# ltk-hall_main_gauss.net
KiCad netlist of a schematic drawn in Altium Designer
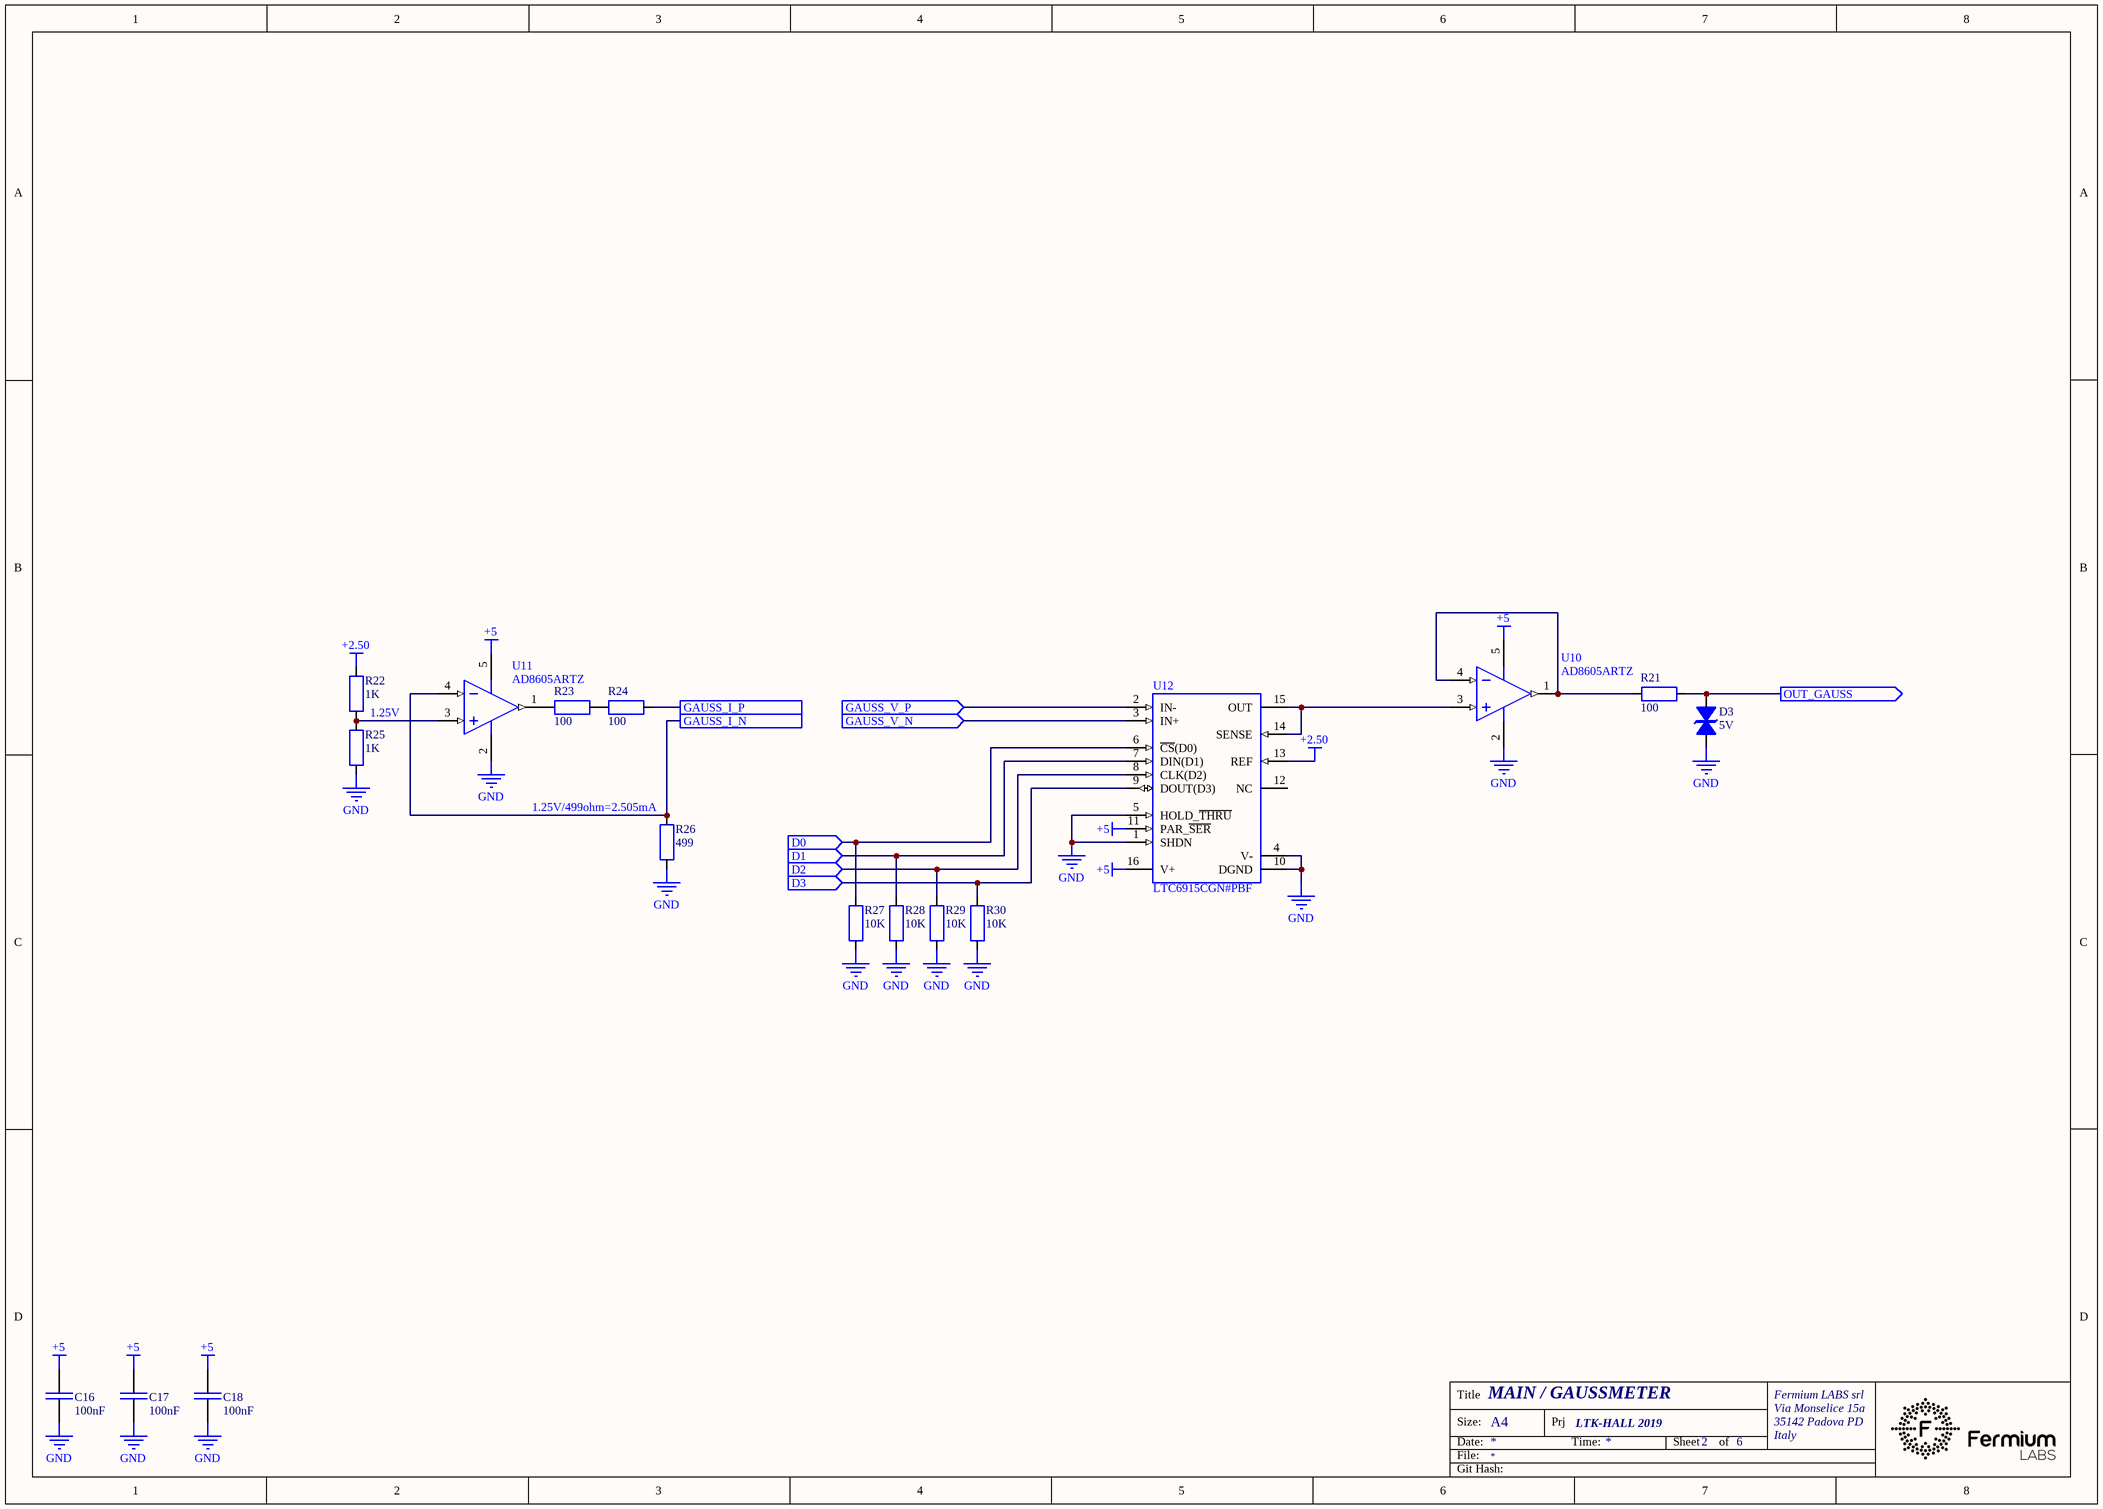
[diagram p0: ltk-hall_main_gauss.SchDoc]

(export (version "E")
  (design (tool "Eeschema 10.0.6"))
  (components
    (comp (ref "C16")
      (value "100nF")
      (footprint "CAP 0603_1608")
      (description "CAP SMD MLCC 100nF 25V 0603 X7R")
      (fields (field (name "PART NUMBER") "02841f84-ac15-41b5-9e17-915f8f067828"))
      (libsource (lib "frmdblib") (part "GENERIC_C"))
    )
    (comp (ref "C17")
      (value "100nF")
      (footprint "CAP 0603_1608")
      (description "CAP SMD MLCC 100nF 25V 0603 X7R")
      (fields (field (name "PART NUMBER") "02841f84-ac15-41b5-9e17-915f8f067828"))
      (libsource (lib "frmdblib") (part "GENERIC_C"))
    )
    (comp (ref "C18")
      (value "100nF")
      (footprint "CAP 0603_1608")
      (description "CAP SMD MLCC 100nF 25V 0603 X7R")
      (fields (field (name "PART NUMBER") "02841f84-ac15-41b5-9e17-915f8f067828"))
      (libsource (lib "frmdblib") (part "GENERIC_C"))
    )
    (comp (ref "D3")
      (value "5V")
      (footprint "SOD523F")
      (description "DIODE SMD TVS 5V BIDIRECTIONAL SOD-523")
      (fields (field (name "PART NUMBER") "daa58212-38e2-4326-a156-8e48058c46f1"))
      (libsource (lib "frmdblib") (part "GENERIC_D_TVS_BI"))
    )
    (comp (ref "R21")
      (value "100")
      (footprint "RES 0603_1608")
      (description "RES SMD 100 OHM 1% 1/10W 0603")
      (fields (field (name "PART NUMBER") "0a6c4b74-f837-4563-b154-6e196d753525"))
      (libsource (lib "frmdblib") (part "GENERIC_R"))
    )
    (comp (ref "R22")
      (value "1K")
      (footprint "RES 0603_1608")
      (description "RES SMD 1K OHM 1% 1/10W 0603")
      (fields (field (name "PART NUMBER") "a678220f-9e9d-4863-a833-9993504f723c"))
      (libsource (lib "frmdblib") (part "GENERIC_R"))
    )
    (comp (ref "R23")
      (value "100")
      (footprint "RES 0603_1608")
      (description "RES SMD 100 OHM 1% 1/10W 0603")
      (fields (field (name "PART NUMBER") "0a6c4b74-f837-4563-b154-6e196d753525"))
      (libsource (lib "frmdblib") (part "GENERIC_R"))
    )
    (comp (ref "R24")
      (value "100")
      (footprint "RES 0603_1608")
      (description "RES SMD 100 OHM 1% 1/10W 0603")
      (fields (field (name "PART NUMBER") "0a6c4b74-f837-4563-b154-6e196d753525"))
      (libsource (lib "frmdblib") (part "GENERIC_R"))
    )
    (comp (ref "R25")
      (value "1K")
      (footprint "RES 0603_1608")
      (description "RES SMD 1K OHM 1% 1/10W 0603")
      (fields (field (name "PART NUMBER") "a678220f-9e9d-4863-a833-9993504f723c"))
      (libsource (lib "frmdblib") (part "GENERIC_R"))
    )
    (comp (ref "R26")
      (value "499")
      (footprint "RES 0603_1608")
      (description "RES SMD 499 OHM 1% 1/10W 0603")
      (fields (field (name "PART NUMBER") "3a10051a-dd65-4121-b0b9-1b40351a1843"))
      (libsource (lib "frmdblib") (part "GENERIC_R"))
    )
    (comp (ref "R27")
      (value "10K")
      (footprint "RES 0603_1608")
      (description "RES SMD 10K OHM 1% 1/10W 0603")
      (fields (field (name "PART NUMBER") "93242766-ba1d-462d-b58f-ce1dfc4129c8"))
      (libsource (lib "frmdblib") (part "GENERIC_R"))
    )
    (comp (ref "R28")
      (value "10K")
      (footprint "RES 0603_1608")
      (description "RES SMD 10K OHM 1% 1/10W 0603")
      (fields (field (name "PART NUMBER") "93242766-ba1d-462d-b58f-ce1dfc4129c8"))
      (libsource (lib "frmdblib") (part "GENERIC_R"))
    )
    (comp (ref "R29")
      (value "10K")
      (footprint "RES 0603_1608")
      (description "RES SMD 10K OHM 1% 1/10W 0603")
      (fields (field (name "PART NUMBER") "93242766-ba1d-462d-b58f-ce1dfc4129c8"))
      (libsource (lib "frmdblib") (part "GENERIC_R"))
    )
    (comp (ref "R30")
      (value "10K")
      (footprint "RES 0603_1608")
      (description "RES SMD 10K OHM 1% 1/10W 0603")
      (fields (field (name "PART NUMBER") "93242766-ba1d-462d-b58f-ce1dfc4129c8"))
      (libsource (lib "frmdblib") (part "GENERIC_R"))
    )
    (comp (ref "U10")
      (value "AD8605ARTZ")
      (footprint "A3DDA0BC-073E-4B18-9613-F713A7EC1E27")
      (description "IC OPAMP 65uV 1pA RRIO 5V 80mA SOT-23-5")
      (fields (field (name "PART NUMBER") "5610e9ea-bca8-49b2-8e5f-11409231f6a4"))
      (libsource (lib "frmdblib") (part "8096D751-9DCE-401B-B65E-AAEE0733EA70"))
    )
    (comp (ref "U11")
      (value "AD8605ARTZ")
      (footprint "A3DDA0BC-073E-4B18-9613-F713A7EC1E27")
      (description "IC OPAMP 65uV 1pA RRIO 5V 80mA SOT-23-5")
      (fields (field (name "PART NUMBER") "5610e9ea-bca8-49b2-8e5f-11409231f6a4"))
      (libsource (lib "frmdblib") (part "8096D751-9DCE-401B-B65E-AAEE0733EA70"))
    )
    (comp (ref "U12")
      (value "LTC6915CGN#PBF")
      (footprint "517EE8A2-9FD8-4174-996D-BDBF76CA3EEB")
      (description "IC PGA G0-4094 SPI-PARALLEL 5V RRIO SSOP-16")
      (fields (field (name "PART NUMBER") "59fe82cd-fd18-4813-9f52-e2e78a460aff"))
      (libsource (lib "frmdblib") (part "092C41BF-C4B2-4D13-B4E9-531E546592A0"))
    )
  )
  (nets
    (net (code "1") (name "+2.50") (class "Default")
      (node (ref "R22") (pin "2") (pintype "passive"))
      (node (ref "U12") (pin "13") (pinfunction "REF_13") (pintype "input"))
    )
    (net (code "2") (name "+5") (class "Default")
      (node (ref "C16") (pin "1") (pintype "passive"))
      (node (ref "C17") (pin "1") (pintype "passive"))
      (node (ref "C18") (pin "1") (pintype "passive"))
      (node (ref "U10") (pin "5") (pinfunction "+V_5") (pintype "power_in"))
      (node (ref "U11") (pin "5") (pinfunction "+V_5") (pintype "power_in"))
      (node (ref "U12") (pin "11") (pinfunction "PAR_~{SER}_11") (pintype "input"))
      (node (ref "U12") (pin "16") (pinfunction "V+_16") (pintype "power_in"))
    )
    (net (code "3") (name "/D0") (class "Default")
      (node (ref "R27") (pin "2") (pintype "passive"))
      (node (ref "U12") (pin "6") (pinfunction "~{CS}(D0)_6") (pintype "input"))
    )
    (net (code "4") (name "/D1") (class "Default")
      (node (ref "R28") (pin "2") (pintype "passive"))
      (node (ref "U12") (pin "7") (pinfunction "DIN(D1)_7") (pintype "input"))
    )
    (net (code "5") (name "/D2") (class "Default")
      (node (ref "R29") (pin "2") (pintype "passive"))
      (node (ref "U12") (pin "8") (pinfunction "CLK(D2)_8") (pintype "input"))
    )
    (net (code "6") (name "/D3") (class "Default")
      (node (ref "R30") (pin "2") (pintype "passive"))
      (node (ref "U12") (pin "9") (pinfunction "DOUT(D3)_9") (pintype "bidirectional"))
    )
    (net (code "7") (name "/GAUSS_I_N") (class "Default")
      (node (ref "R26") (pin "2") (pintype "passive"))
      (node (ref "U11") (pin "4") (pinfunction "-IN_4") (pintype "input"))
    )
    (net (code "8") (name "/GAUSS_I_P") (class "Default") (node (ref "R24") (pin "2") (pintype "passive")))
    (net (code "9") (name "/GAUSS_V_N") (class "Default")
      (node (ref "U12") (pin "3") (pinfunction "IN+_3") (pintype "input"))
    )
    (net (code "10") (name "/GAUSS_V_P") (class "Default")
      (node (ref "U12") (pin "2") (pinfunction "IN-_2") (pintype "input"))
    )
    (net (code "11") (name "/OUT_GAUSS") (class "Default")
      (node (ref "D3") (pin "1") (pintype "passive"))
      (node (ref "R21") (pin "2") (pintype "passive"))
    )
    (net (code "12") (name "GND") (class "Default")
      (node (ref "C16") (pin "2") (pintype "passive"))
      (node (ref "C17") (pin "2") (pintype "passive"))
      (node (ref "C18") (pin "2") (pintype "passive"))
      (node (ref "D3") (pin "2") (pintype "passive"))
      (node (ref "R25") (pin "1") (pintype "passive"))
      (node (ref "R26") (pin "1") (pintype "passive"))
      (node (ref "R27") (pin "1") (pintype "passive"))
      (node (ref "R28") (pin "1") (pintype "passive"))
      (node (ref "R29") (pin "1") (pintype "passive"))
      (node (ref "R30") (pin "1") (pintype "passive"))
      (node (ref "U10") (pin "2") (pinfunction "-V_2") (pintype "power_in"))
      (node (ref "U11") (pin "2") (pinfunction "-V_2") (pintype "power_in"))
      (node (ref "U12") (pin "1") (pinfunction "SHDN_1") (pintype "input"))
      (node (ref "U12") (pin "10") (pinfunction "DGND_10") (pintype "power_in"))
      (node (ref "U12") (pin "4") (pinfunction "V-_4") (pintype "power_in"))
      (node (ref "U12") (pin "5") (pinfunction "HOLD_~{THRU}_5") (pintype "input"))
    )
    (net (code "13") (name "Net-(R23-Pad2)") (class "Default")
      (node (ref "R23") (pin "2") (pintype "passive"))
      (node (ref "R24") (pin "1") (pintype "passive"))
    )
    (net (code "14") (name "Net-(U10-+IN)") (class "Default")
      (node (ref "U10") (pin "3") (pinfunction "+IN_3") (pintype "input"))
      (node (ref "U12") (pin "14") (pinfunction "SENSE_14") (pintype "input"))
      (node (ref "U12") (pin "15") (pinfunction "OUT_15") (pintype "tri_state"))
    )
    (net (code "15") (name "Net-(U10--IN)") (class "Default")
      (node (ref "R21") (pin "1") (pintype "passive"))
      (node (ref "U10") (pin "1") (pinfunction "OUT_1") (pintype "output"))
      (node (ref "U10") (pin "4") (pinfunction "-IN_4") (pintype "input"))
    )
    (net (code "16") (name "Net-(U11-+IN)") (class "Default")
      (node (ref "R22") (pin "1") (pintype "passive"))
      (node (ref "R25") (pin "2") (pintype "passive"))
      (node (ref "U11") (pin "3") (pinfunction "+IN_3") (pintype "input"))
    )
    (net (code "17") (name "Net-(U11-OUT)") (class "Default")
      (node (ref "R23") (pin "1") (pintype "passive"))
      (node (ref "U11") (pin "1") (pinfunction "OUT_1") (pintype "output"))
    )
    (net (code "18") (name "unconnected-(U12-NC-Pad12)") (class "Default")
      (node (ref "U12") (pin "12") (pinfunction "NC_12") (pintype "passive"))
    )
  )
)
